# RiskChemi_Monitor_V1_04M1.net
KiCad netlist of a schematic drawn in Altium Designer
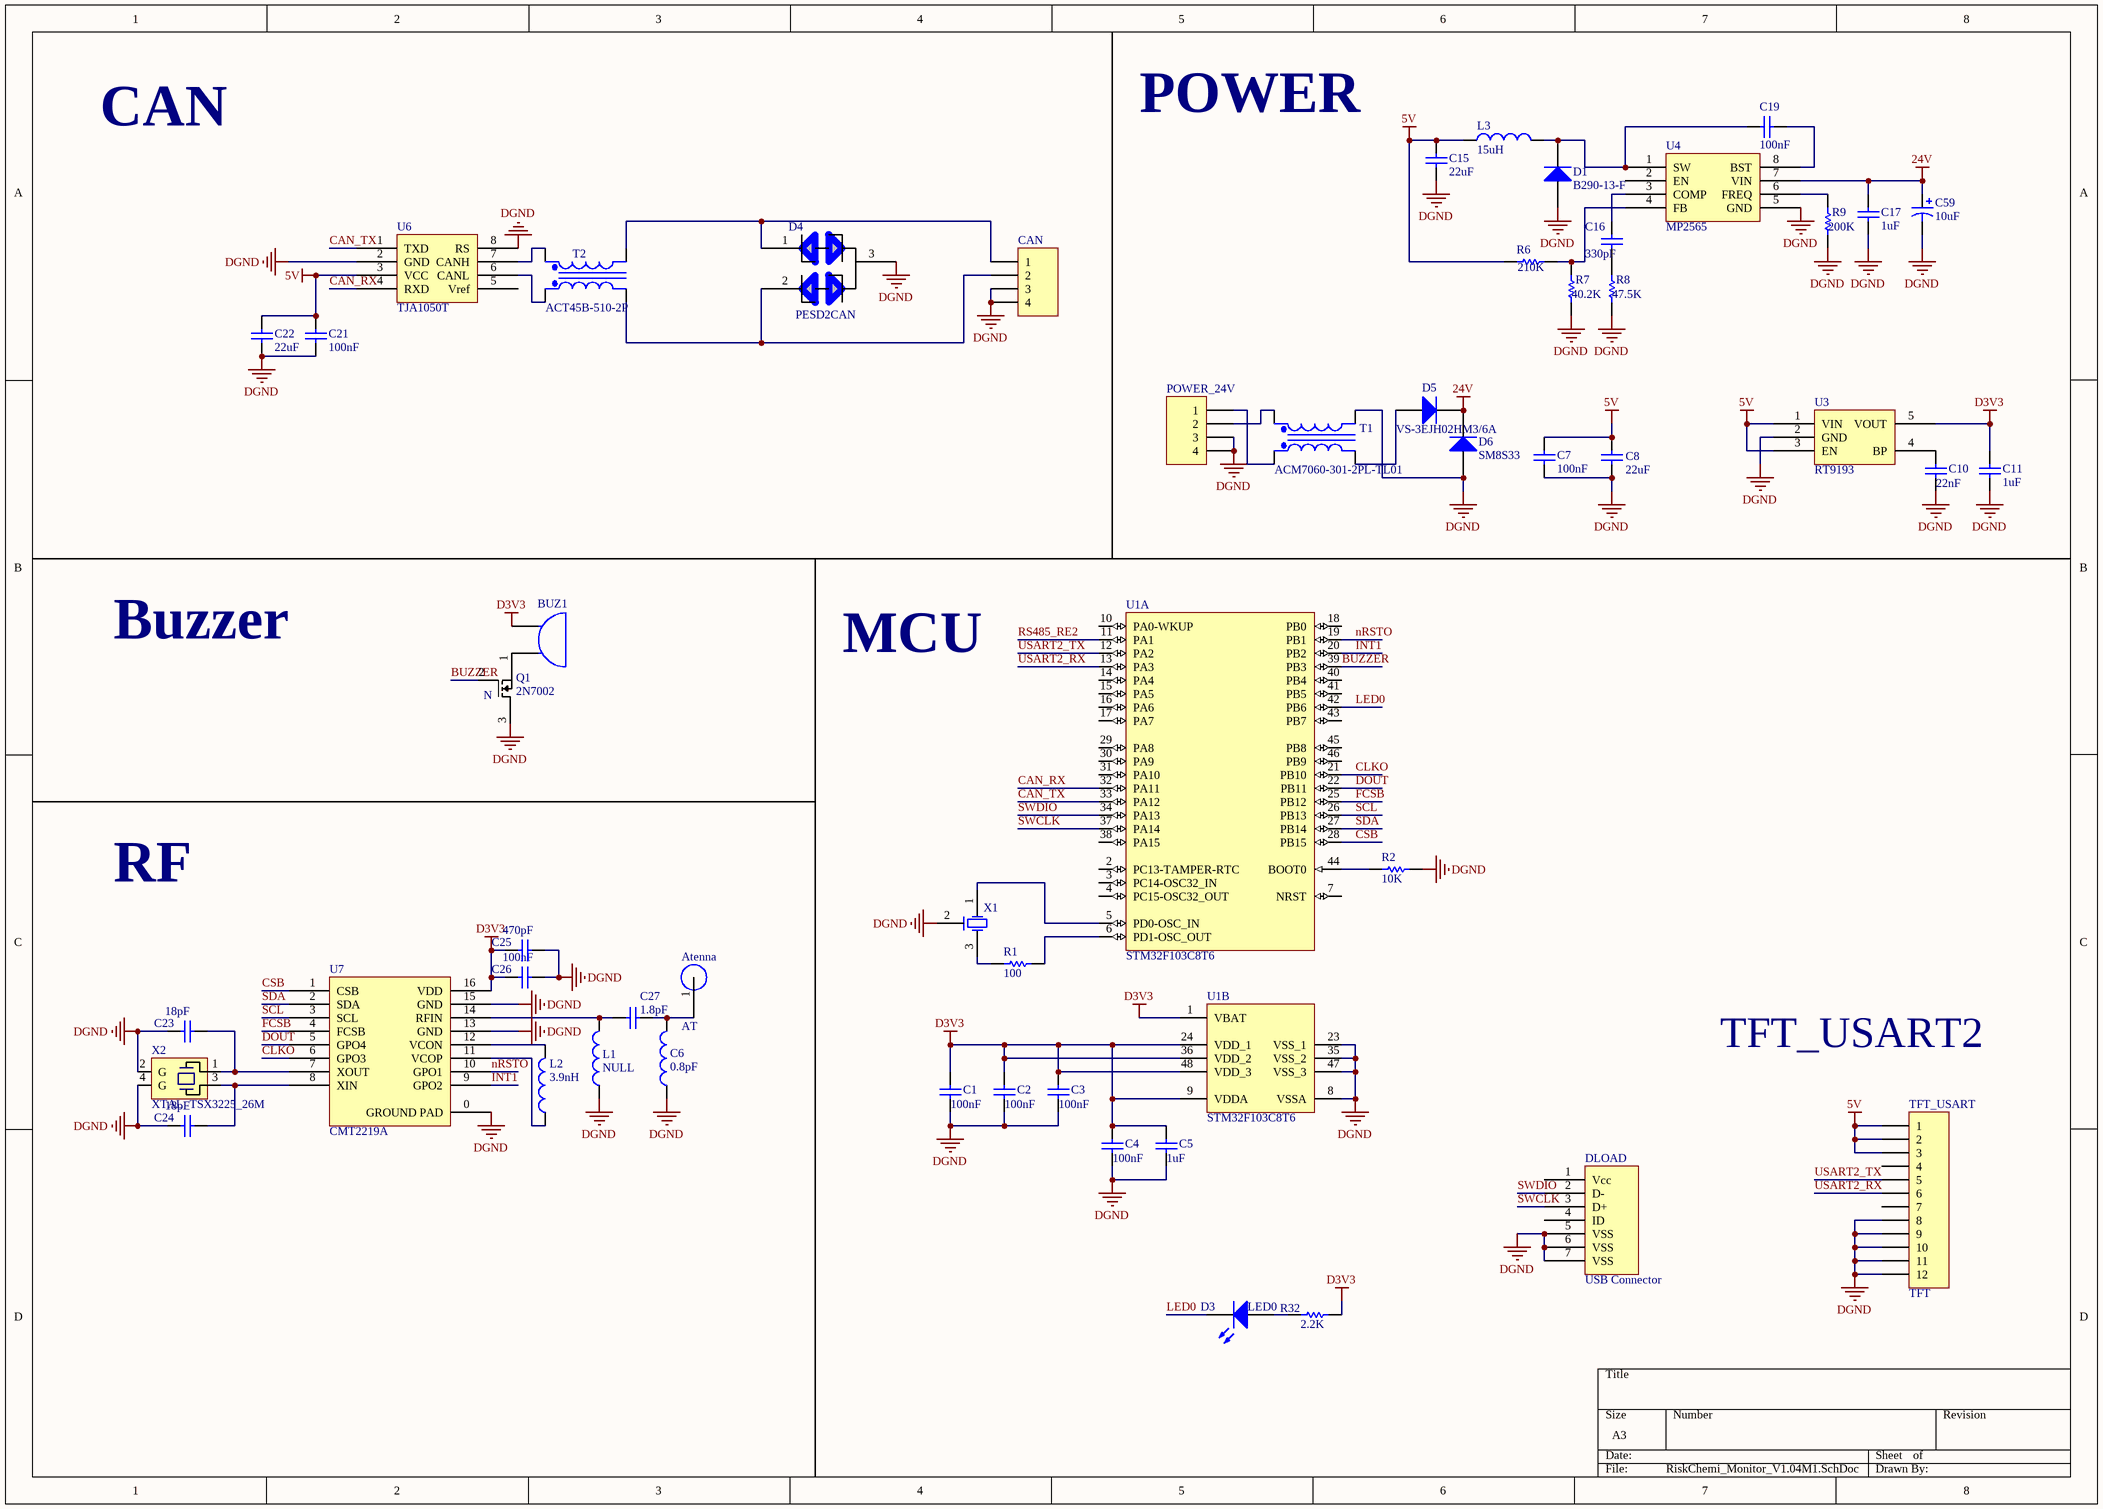
[diagram p0: RiskChemi_Monitor_V1.04M1.SchDoc]

(export (version "E")
  (design (tool "Eeschema 10.0.6"))
  (components
    (comp (ref "Atenna") (value "AT") (footprint "433MHz Atenna") (libsource (lib "MySchlib1") (part "AT")))
    (comp (ref "BUZ1")
      (value "BUZZER")
      (footprint "BUZ0905")
      (description "Buzzer")
      (libsource (lib "杂元件库") (part "BUZZER"))
    )
    (comp (ref "C1")
      (value "100nF")
      (footprint "0603")
      (description "Capacitor")
      (fields (field (name "PUBLISHER") "Altium Limited"))
      (libsource (lib "Miscellaneous Devices") (part "Cap"))
    )
    (comp (ref "C2")
      (value "100nF")
      (footprint "0603")
      (description "Capacitor")
      (fields (field (name "PUBLISHER") "Altium Limited"))
      (libsource (lib "Miscellaneous Devices") (part "Cap"))
    )
    (comp (ref "C3")
      (value "100nF")
      (footprint "0603")
      (description "Capacitor")
      (fields (field (name "PUBLISHER") "Altium Limited"))
      (libsource (lib "Miscellaneous Devices") (part "Cap"))
    )
    (comp (ref "C4")
      (value "100nF")
      (footprint "0603")
      (description "Capacitor")
      (fields (field (name "PUBLISHER") "Altium Limited"))
      (libsource (lib "Miscellaneous Devices") (part "Cap"))
    )
    (comp (ref "C5")
      (value "1uF")
      (footprint "0603")
      (description "Capacitor")
      (fields (field (name "PUBLISHER") "Altium Limited"))
      (libsource (lib "Miscellaneous Devices") (part "Cap"))
    )
    (comp (ref "C6")
      (value "0.8pF")
      (footprint "Miscellaneous Devices:0402")
      (description "Inductor")
      (fields (field (name "PUBLISHER") "Altium Limited"))
      (libsource (lib "Miscellaneous Devices") (part "Inductor"))
    )
    (comp (ref "C7")
      (value "100nF")
      (footprint "0805")
      (description "Capacitor,100V")
      (fields (field (name "PUBLISHER") "Altium Limited"))
      (libsource (lib "Miscellaneous Devices") (part "Cap"))
    )
    (comp (ref "C8")
      (value "22uF")
      (footprint "0805")
      (description "Capacitor")
      (fields (field (name "PUBLISHER") "Altium Limited"))
      (libsource (lib "Miscellaneous Devices") (part "Cap"))
    )
    (comp (ref "C10")
      (value "22nF")
      (footprint "BinFeng:0603")
      (description "Capacitor")
      (fields (field (name "PUBLISHER") "Altium Limited"))
      (libsource (lib "Miscellaneous Devices") (part "Cap"))
    )
    (comp (ref "C11")
      (value "1uF")
      (footprint "BinFeng:0603")
      (description "Capacitor")
      (fields (field (name "PUBLISHER") "Altium Limited"))
      (libsource (lib "Miscellaneous Devices") (part "Cap"))
    )
    (comp (ref "C15")
      (value "22uF")
      (footprint "0805")
      (description "Capacitor,50V")
      (fields (field (name "PUBLISHER") "Altium Limited"))
      (libsource (lib "Miscellaneous Devices") (part "Cap"))
    )
    (comp (ref "C16")
      (value "330pF")
      (footprint "BinFeng:0402")
      (description "Capacitor")
      (fields (field (name "PUBLISHER") "Altium Limited"))
      (libsource (lib "Miscellaneous Devices") (part "Cap"))
    )
    (comp (ref "C17")
      (value "1uF")
      (footprint "0805")
      (description "Capacitor,100V")
      (fields (field (name "PUBLISHER") "Altium Limited"))
      (libsource (lib "Miscellaneous Devices") (part "Cap"))
    )
    (comp (ref "C19")
      (value "100nF")
      (footprint "BinFeng:0402")
      (description "Capacitor")
      (fields (field (name "PUBLISHER") "Altium Limited"))
      (libsource (lib "Miscellaneous Devices") (part "Cap"))
    )
    (comp (ref "C21")
      (value "100nF")
      (footprint "0603")
      (description "Capacitor")
      (fields (field (name "PUBLISHER") "Altium Limited"))
      (libsource (lib "Miscellaneous Devices") (part "Cap"))
    )
    (comp (ref "C22")
      (value "22uF")
      (footprint "0805")
      (description "Capacitor")
      (fields (field (name "PUBLISHER") "Altium Limited"))
      (libsource (lib "Miscellaneous Devices") (part "Cap"))
    )
    (comp (ref "C23")
      (value "18pF")
      (footprint "BinFeng:0402")
      (description "Capacitor")
      (fields (field (name "PUBLISHER") "Altium Limited"))
      (libsource (lib "Miscellaneous Devices") (part "Cap"))
    )
    (comp (ref "C24")
      (value "18pF")
      (footprint "BinFeng:0402")
      (description "Capacitor")
      (fields (field (name "PUBLISHER") "Altium Limited"))
      (libsource (lib "Miscellaneous Devices") (part "Cap"))
    )
    (comp (ref "C25")
      (value "470pF")
      (footprint "BinFeng:0402")
      (description "Capacitor")
      (fields (field (name "PUBLISHER") "Altium Limited"))
      (libsource (lib "Miscellaneous Devices") (part "Cap"))
    )
    (comp (ref "C26")
      (value "100nF")
      (footprint "BinFeng:0603")
      (description "Capacitor")
      (fields (field (name "PUBLISHER") "Altium Limited"))
      (libsource (lib "Miscellaneous Devices") (part "Cap"))
    )
    (comp (ref "C27")
      (value "1.8pF")
      (footprint "BinFeng:nosilk_0402")
      (description "Capacitor")
      (fields (field (name "PUBLISHER") "Altium Limited"))
      (libsource (lib "Miscellaneous Devices") (part "Cap"))
    )
    (comp (ref "C59")
      (value "10uF")
      (footprint "6032_pol")
      (description "Polarized Capacitor (Radial)")
      (fields (field (name "PUBLISHER") "Altium Limited"))
      (libsource (lib "Miscellaneous Devices") (part "Cap Pol1"))
    )
    (comp (ref "CAN")
      (value "Header 4")
      (footprint "C3000VS")
      (description "Header, 4-Pin")
      (fields (field (name "PUBLISHER") "Altium Limited"))
      (libsource (lib "Miscellaneous Connectors") (part "Header 4"))
    )
    (comp (ref "D1")
      (value "B290-13-F")
      (footprint "back:B290")
      (description "Default Diode")
      (fields (field (name "PUBLISHER") "Altium Limited"))
      (libsource (lib "Miscellaneous Devices") (part "Diode"))
    )
    (comp (ref "D3")
      (value "LED0")
      (footprint "LED")
      (description "green LED")
      (fields (field (name "PUBLISHER") "Altium Limited"))
      (libsource (lib "Miscellaneous Devices") (part "LED0"))
    )
    (comp (ref "D4")
      (value "PESD2CAN")
      (footprint "SOT23")
      (libsource (lib "BinFeng_Connectors") (part "PESD1CAN"))
    )
    (comp (ref "D5")
      (value "VS-3EJH02HM3/6A")
      (footprint "back:B290")
      (description "1 Amp General Purpose Rectifier")
      (fields (field (name "PUBLISHER") "Altium Limited"))
      (libsource (lib "Miscellaneous Devices") (part "Diode 1N4007"))
    )
    (comp (ref "D6")
      (value "SM8S33")
      (footprint "SM8S")
      (description "1 Amp General Purpose Rectifier")
      (fields (field (name "PUBLISHER") "Altium Limited"))
      (libsource (lib "Miscellaneous Devices") (part "Diode 1N4007"))
    )
    (comp (ref "DLOAD")
      (value "USB Connector")
      (footprint "Mini_USB")
      (libsource (lib "BinFeng_Connectors") (part "Component_1"))
    )
    (comp (ref "L1")
      (value "NULL")
      (footprint "Miscellaneous Devices:0402")
      (description "Inductor")
      (fields (field (name "PUBLISHER") "Altium Limited"))
      (libsource (lib "Miscellaneous Devices") (part "Inductor"))
    )
    (comp (ref "L2")
      (value "3.9nH")
      (footprint "BinFeng:0603")
      (description "Inductor")
      (fields (field (name "PUBLISHER") "Altium Limited"))
      (libsource (lib "Miscellaneous Devices") (part "Inductor"))
    )
    (comp (ref "L3")
      (value "15uH")
      (footprint "4*4 Inductor")
      (description "Inductor, 1A")
      (fields (field (name "PUBLISHER") "Altium Limited"))
      (libsource (lib "Miscellaneous Devices") (part "Inductor"))
    )
    (comp (ref "POWER_24V")
      (value "Header 4")
      (footprint "C3000VS")
      (description "Header, 4-Pin")
      (fields (field (name "PUBLISHER") "Altium Limited"))
      (libsource (lib "") (part "Header 4_1"))
    )
    (comp (ref "Q1") (value "2N7002") (footprint "2N7002") (libsource (lib "seeder") (part "N-MOSFET")))
    (comp (ref "R1")
      (value "100")
      (footprint "back:0603")
      (description "Resistor")
      (fields (field (name "PUBLISHER") "Altium Limited"))
      (libsource (lib "Miscellaneous Devices") (part "Res1"))
    )
    (comp (ref "R2")
      (value "10K")
      (footprint "back:0603")
      (description "Resistor")
      (fields (field (name "PUBLISHER") "Altium Limited"))
      (libsource (lib "Miscellaneous Devices") (part "Res1"))
    )
    (comp (ref "R6")
      (value "210K")
      (footprint "BinFeng:0402")
      (description "Resistor")
      (fields (field (name "PUBLISHER") "Altium Limited"))
      (libsource (lib "Miscellaneous Devices") (part "Res1"))
    )
    (comp (ref "R7")
      (value "40.2K")
      (footprint "BinFeng:0402")
      (description "Resistor")
      (fields (field (name "PUBLISHER") "Altium Limited"))
      (libsource (lib "Miscellaneous Devices") (part "Res1"))
    )
    (comp (ref "R8")
      (value "47.5K")
      (footprint "BinFeng:0402")
      (description "Resistor")
      (fields (field (name "PUBLISHER") "Altium Limited"))
      (libsource (lib "Miscellaneous Devices") (part "Res1"))
    )
    (comp (ref "R9")
      (value "200K")
      (footprint "BinFeng:0402")
      (description "Resistor")
      (fields (field (name "PUBLISHER") "Altium Limited"))
      (libsource (lib "Miscellaneous Devices") (part "Res1"))
    )
    (comp (ref "R32")
      (value "2.2K")
      (footprint "BinFeng:0603")
      (description "Resistor")
      (fields (field (name "PUBLISHER") "Altium Limited"))
      (libsource (lib "Miscellaneous Devices") (part "Res1"))
    )
    (comp (ref "T1")
      (value "ACM7060-301-2PL-TL01")
      (footprint "ACM7060-301-2P-TL01")
      (description "Transformer (Equivalent Circuit Model)")
      (fields (field (name "PUBLISHER") "Altium Limited"))
      (libsource (lib "Miscellaneous Devices") (part "Trans Eq"))
    )
    (comp (ref "T2")
      (value "ACT45B-510-2P")
      (footprint "ACT45B-510-2P")
      (description "Transformer (Equivalent Circuit Model)")
      (fields (field (name "PUBLISHER") "Altium Limited"))
      (libsource (lib "Miscellaneous Devices") (part "Trans Eq"))
    )
    (comp (ref "TFT_USART")
      (value "TFT")
      (footprint "FCC_10pin_1mm")
      (description "Header, 12-Pin")
      (fields (field (name "PUBLISHER") "Altium Limited"))
      (libsource (lib "Miscellaneous Connectors") (part "Header 12"))
    )
    (comp (ref "U1")
      (value "STM32F103C8T6")
      (footprint "STM-LQFP48_N")
      (libsource (lib "STMicroelectronics STM32 F1") (part "STM32F103C8T6"))
    )
    (comp (ref "U3") (value "RT9193") (footprint "SOT-23-5") (libsource (lib "BinFeng_IC") (part "RT9193")))
    (comp (ref "U4")
      (value "MP2565")
      (footprint "SO8")
      (description "DCDC 4.5V~28V input 1.8V ~5V output low power")
      (libsource (lib "BinFeng_IC") (part "MP1584"))
    )
    (comp (ref "U6")
      (value "TJA1050T")
      (footprint "SO8")
      (description "CAN Tranceiver")
      (libsource (lib "BinFeng_IC") (part "TJA1050T"))
    )
    (comp (ref "U7")
      (value "CMT2219A")
      (footprint "back:QFN16")
      (libsource (lib "BinFeng_IC") (part "CMT2219A"))
    )
    (comp (ref "X1") (value "8M smd") (footprint "8Mhz_XTAL") (libsource (lib "Schlib1") (part "8M smd")))
    (comp (ref "X2")
      (value "XTAL_TSX3225_26M")
      (footprint "XTAL3225")
      (libsource (lib "BinFeng_IC") (part "XTAL_Negative"))
    )
  )
  (nets
    (net (code "1") (name "/BUZZER") (class "Default")
      (node (ref "Q1") (pin "2") (pinfunction "G_2") (pintype "passive"))
      (node (ref "U1") (pin "39") (pinfunction "PB3_39") (pintype "bidirectional"))
    )
    (net (code "2") (name "/CAN_RX") (class "Default")
      (node (ref "U1") (pin "32") (pinfunction "PA11_32") (pintype "bidirectional"))
      (node (ref "U6") (pin "4") (pinfunction "RXD_4") (pintype "passive"))
    )
    (net (code "3") (name "/CAN_TX") (class "Default")
      (node (ref "U1") (pin "33") (pinfunction "PA12_33") (pintype "bidirectional"))
      (node (ref "U6") (pin "1") (pinfunction "TXD_1") (pintype "passive"))
    )
    (net (code "4") (name "/CLKO") (class "Default")
      (node (ref "U1") (pin "21") (pinfunction "PB10_21") (pintype "bidirectional"))
      (node (ref "U7") (pin "6") (pinfunction "GPO3_6") (pintype "passive"))
    )
    (net (code "5") (name "/CSB") (class "Default")
      (node (ref "U1") (pin "28") (pinfunction "PB15_28") (pintype "bidirectional"))
      (node (ref "U7") (pin "1") (pinfunction "CSB_1") (pintype "passive"))
    )
    (net (code "6") (name "/DOUT") (class "Default")
      (node (ref "U1") (pin "22") (pinfunction "PB11_22") (pintype "bidirectional"))
      (node (ref "U7") (pin "5") (pinfunction "GPO4_5") (pintype "passive"))
    )
    (net (code "7") (name "/FCSB") (class "Default")
      (node (ref "U1") (pin "25") (pinfunction "PB12_25") (pintype "bidirectional"))
      (node (ref "U7") (pin "4") (pinfunction "FCSB_4") (pintype "passive"))
    )
    (net (code "8") (name "/INT1") (class "Default")
      (node (ref "U1") (pin "20") (pinfunction "PB2_20") (pintype "bidirectional"))
      (node (ref "U7") (pin "9") (pinfunction "GPO2_9") (pintype "passive"))
    )
    (net (code "9") (name "/LED0") (class "Default")
      (node (ref "D3") (pin "2") (pinfunction "K_2") (pintype "passive"))
      (node (ref "U1") (pin "42") (pinfunction "PB6_42") (pintype "bidirectional"))
    )
    (net (code "10") (name "/RS485_RE2") (class "Default")
      (node (ref "U1") (pin "11") (pinfunction "PA1_11") (pintype "bidirectional"))
    )
    (net (code "11") (name "/SCL") (class "Default")
      (node (ref "U1") (pin "26") (pinfunction "PB13_26") (pintype "bidirectional"))
      (node (ref "U7") (pin "3") (pinfunction "SCL_3") (pintype "passive"))
    )
    (net (code "12") (name "/SDA") (class "Default")
      (node (ref "U1") (pin "27") (pinfunction "PB14_27") (pintype "bidirectional"))
      (node (ref "U7") (pin "2") (pinfunction "SDA_2") (pintype "passive"))
    )
    (net (code "13") (name "/SWCLK") (class "Default")
      (node (ref "DLOAD") (pin "3") (pinfunction "D+_3") (pintype "passive"))
      (node (ref "U1") (pin "37") (pinfunction "PA14_37") (pintype "bidirectional"))
    )
    (net (code "14") (name "/SWDIO") (class "Default")
      (node (ref "DLOAD") (pin "2") (pinfunction "D-_2") (pintype "passive"))
      (node (ref "U1") (pin "34") (pinfunction "PA13_34") (pintype "bidirectional"))
    )
    (net (code "15") (name "/USART2_RX") (class "Default")
      (node (ref "TFT_USART") (pin "6") (pinfunction "6_6") (pintype "passive"))
      (node (ref "U1") (pin "13") (pinfunction "PA3_13") (pintype "bidirectional"))
    )
    (net (code "16") (name "/USART2_TX") (class "Default")
      (node (ref "TFT_USART") (pin "5") (pinfunction "5_5") (pintype "passive"))
      (node (ref "U1") (pin "12") (pinfunction "PA2_12") (pintype "bidirectional"))
    )
    (net (code "17") (name "/nRSTO") (class "Default")
      (node (ref "U1") (pin "19") (pinfunction "PB1_19") (pintype "bidirectional"))
      (node (ref "U7") (pin "10") (pinfunction "GPO1_10") (pintype "passive"))
    )
    (net (code "18") (name "5V") (class "Default")
      (node (ref "C15") (pin "2") (pinfunction "2_2") (pintype "passive"))
      (node (ref "C21") (pin "1") (pinfunction "1_1") (pintype "passive"))
      (node (ref "C22") (pin "2") (pinfunction "2_2") (pintype "passive"))
      (node (ref "C7") (pin "2") (pinfunction "2_2") (pintype "passive"))
      (node (ref "C8") (pin "2") (pinfunction "2_2") (pintype "passive"))
      (node (ref "L3") (pin "1") (pinfunction "1_1") (pintype "passive"))
      (node (ref "R6") (pin "2") (pinfunction "2_2") (pintype "passive"))
      (node (ref "TFT_USART") (pin "1") (pinfunction "1_1") (pintype "passive"))
      (node (ref "TFT_USART") (pin "2") (pinfunction "2_2") (pintype "passive"))
      (node (ref "TFT_USART") (pin "3") (pinfunction "3_3") (pintype "passive"))
      (node (ref "U3") (pin "1") (pinfunction "VIN_1") (pintype "passive"))
      (node (ref "U3") (pin "3") (pinfunction "EN_3") (pintype "passive"))
      (node (ref "U6") (pin "3") (pinfunction "VCC_3") (pintype "passive"))
    )
    (net (code "19") (name "24V") (class "Default")
      (node (ref "C17") (pin "2") (pinfunction "2_2") (pintype "passive"))
      (node (ref "C59") (pin "1") (pinfunction "1_1") (pintype "passive"))
      (node (ref "D5") (pin "2") (pinfunction "K_2") (pintype "passive"))
      (node (ref "D6") (pin "2") (pinfunction "K_2") (pintype "passive"))
      (node (ref "U4") (pin "7") (pinfunction "VIN_7") (pintype "passive"))
    )
    (net (code "20") (name "D3V3") (class "Default")
      (node (ref "BUZ1") (pin "1") (pinfunction "A_1") (pintype "passive"))
      (node (ref "C1") (pin "2") (pinfunction "2_2") (pintype "passive"))
      (node (ref "C11") (pin "2") (pinfunction "2_2") (pintype "passive"))
      (node (ref "C2") (pin "2") (pinfunction "2_2") (pintype "passive"))
      (node (ref "C25") (pin "2") (pinfunction "2_2") (pintype "passive"))
      (node (ref "C26") (pin "2") (pinfunction "2_2") (pintype "passive"))
      (node (ref "C3") (pin "2") (pinfunction "2_2") (pintype "passive"))
      (node (ref "C4") (pin "2") (pinfunction "2_2") (pintype "passive"))
      (node (ref "C5") (pin "2") (pinfunction "2_2") (pintype "passive"))
      (node (ref "R32") (pin "1") (pinfunction "1_1") (pintype "passive"))
      (node (ref "U1") (pin "1") (pinfunction "VBAT_1") (pintype "power_in"))
      (node (ref "U1") (pin "24") (pinfunction "VDD_1_24") (pintype "power_in"))
      (node (ref "U1") (pin "36") (pinfunction "VDD_2_36") (pintype "power_in"))
      (node (ref "U1") (pin "48") (pinfunction "VDD_3_48") (pintype "power_in"))
      (node (ref "U1") (pin "9") (pinfunction "VDDA_9") (pintype "power_in"))
      (node (ref "U3") (pin "5") (pinfunction "VOUT_5") (pintype "passive"))
      (node (ref "U7") (pin "16") (pinfunction "VDD_16") (pintype "passive"))
    )
    (net (code "21") (name "DGND") (class "Default")
      (node (ref "C1") (pin "1") (pinfunction "1_1") (pintype "passive"))
      (node (ref "C10") (pin "1") (pinfunction "1_1") (pintype "passive"))
      (node (ref "C11") (pin "1") (pinfunction "1_1") (pintype "passive"))
      (node (ref "C15") (pin "1") (pinfunction "1_1") (pintype "passive"))
      (node (ref "C17") (pin "1") (pinfunction "1_1") (pintype "passive"))
      (node (ref "C2") (pin "1") (pinfunction "1_1") (pintype "passive"))
      (node (ref "C21") (pin "2") (pinfunction "2_2") (pintype "passive"))
      (node (ref "C22") (pin "1") (pinfunction "1_1") (pintype "passive"))
      (node (ref "C23") (pin "2") (pinfunction "2_2") (pintype "passive"))
      (node (ref "C24") (pin "2") (pinfunction "2_2") (pintype "passive"))
      (node (ref "C25") (pin "1") (pinfunction "1_1") (pintype "passive"))
      (node (ref "C26") (pin "1") (pinfunction "1_1") (pintype "passive"))
      (node (ref "C3") (pin "1") (pinfunction "1_1") (pintype "passive"))
      (node (ref "C4") (pin "1") (pinfunction "1_1") (pintype "passive"))
      (node (ref "C5") (pin "1") (pinfunction "1_1") (pintype "passive"))
      (node (ref "C59") (pin "2") (pinfunction "2_2") (pintype "passive"))
      (node (ref "C6") (pin "1") (pinfunction "1_1") (pintype "passive"))
      (node (ref "C7") (pin "1") (pinfunction "1_1") (pintype "passive"))
      (node (ref "C8") (pin "1") (pinfunction "1_1") (pintype "passive"))
      (node (ref "CAN") (pin "3") (pinfunction "3_3") (pintype "passive"))
      (node (ref "CAN") (pin "4") (pinfunction "4_4") (pintype "passive"))
      (node (ref "D1") (pin "1") (pinfunction "A_1") (pintype "passive"))
      (node (ref "D4") (pin "3") (pinfunction "13_3") (pintype "passive"))
      (node (ref "D6") (pin "1") (pinfunction "A_1") (pintype "passive"))
      (node (ref "DLOAD") (pin "5") (pinfunction "VSS_5") (pintype "passive"))
      (node (ref "DLOAD") (pin "6") (pinfunction "VSS_6") (pintype "passive"))
      (node (ref "DLOAD") (pin "7") (pinfunction "VSS_7") (pintype "passive"))
      (node (ref "L1") (pin "1") (pinfunction "1_1") (pintype "passive"))
      (node (ref "POWER_24V") (pin "3") (pinfunction "3_3") (pintype "passive"))
      (node (ref "POWER_24V") (pin "4") (pinfunction "4_4") (pintype "passive"))
      (node (ref "Q1") (pin "3") (pinfunction "S_3") (pintype "passive"))
      (node (ref "R2") (pin "2") (pinfunction "2_2") (pintype "passive"))
      (node (ref "R7") (pin "1") (pinfunction "1_1") (pintype "passive"))
      (node (ref "R8") (pin "1") (pinfunction "1_1") (pintype "passive"))
      (node (ref "R9") (pin "1") (pinfunction "1_1") (pintype "passive"))
      (node (ref "T1") (pin "4") (pinfunction "Sec-_4") (pintype "passive"))
      (node (ref "TFT_USART") (pin "10") (pinfunction "10_10") (pintype "passive"))
      (node (ref "TFT_USART") (pin "11") (pinfunction "11_11") (pintype "passive"))
      (node (ref "TFT_USART") (pin "12") (pinfunction "12_12") (pintype "passive"))
      (node (ref "TFT_USART") (pin "8") (pinfunction "8_8") (pintype "passive"))
      (node (ref "TFT_USART") (pin "9") (pinfunction "9_9") (pintype "passive"))
      (node (ref "U1") (pin "23") (pinfunction "VSS_1_23") (pintype "power_in"))
      (node (ref "U1") (pin "35") (pinfunction "VSS_2_35") (pintype "power_in"))
      (node (ref "U1") (pin "47") (pinfunction "VSS_3_47") (pintype "power_in"))
      (node (ref "U1") (pin "8") (pinfunction "VSSA_8") (pintype "power_in"))
      (node (ref "U3") (pin "2") (pinfunction "GND_2") (pintype "passive"))
      (node (ref "U4") (pin "5") (pinfunction "GND_5") (pintype "passive"))
      (node (ref "U6") (pin "2") (pinfunction "GND_2") (pintype "passive"))
      (node (ref "U6") (pin "8") (pinfunction "RS_8") (pintype "passive"))
      (node (ref "U7") (pin "0") (pinfunction "GROUND_PAD_0") (pintype "passive"))
      (node (ref "U7") (pin "13") (pinfunction "GND_13") (pintype "passive"))
      (node (ref "U7") (pin "15") (pinfunction "GND_15") (pintype "passive"))
      (node (ref "X1") (pin "2") (pinfunction "GND_2") (pintype "passive"))
      (node (ref "X2") (pin "2") (pinfunction "G_2") (pintype "passive"))
      (node (ref "X2") (pin "4") (pinfunction "G_4") (pintype "passive"))
    )
    (net (code "22") (name "Net-(Atenna-Pad1)") (class "Default")
      (node (ref "Atenna") (pin "1") (pinfunction "1_1") (pintype "passive"))
      (node (ref "C27") (pin "1") (pinfunction "1_1") (pintype "passive"))
      (node (ref "C6") (pin "2") (pinfunction "2_2") (pintype "passive"))
    )
    (net (code "23") (name "Net-(BUZ1-B)") (class "Default")
      (node (ref "BUZ1") (pin "2") (pinfunction "B_2") (pintype "passive"))
      (node (ref "Q1") (pin "1") (pinfunction "D_1") (pintype "passive"))
    )
    (net (code "24") (name "Net-(C16-Pad2)") (class "Default")
      (node (ref "C16") (pin "2") (pinfunction "2_2") (pintype "passive"))
      (node (ref "R8") (pin "2") (pinfunction "2_2") (pintype "passive"))
    )
    (net (code "25") (name "Net-(D1-K)") (class "Default")
      (node (ref "C19") (pin "2") (pinfunction "2_2") (pintype "passive"))
      (node (ref "D1") (pin "2") (pinfunction "K_2") (pintype "passive"))
      (node (ref "L3") (pin "2") (pinfunction "2_2") (pintype "passive"))
      (node (ref "U4") (pin "1") (pinfunction "SW_1") (pintype "passive"))
    )
    (net (code "26") (name "Net-(D3-A)") (class "Default")
      (node (ref "D3") (pin "1") (pinfunction "A_1") (pintype "passive"))
      (node (ref "R32") (pin "2") (pinfunction "2_2") (pintype "passive"))
    )
    (net (code "27") (name "Net-(D4-11)") (class "Default")
      (node (ref "CAN") (pin "1") (pinfunction "1_1") (pintype "passive"))
      (node (ref "D4") (pin "1") (pinfunction "11_1") (pintype "passive"))
      (node (ref "T2") (pin "4") (pinfunction "Sec-_4") (pintype "passive"))
    )
    (net (code "28") (name "Net-(D4-12)") (class "Default")
      (node (ref "CAN") (pin "2") (pinfunction "2_2") (pintype "passive"))
      (node (ref "D4") (pin "2") (pinfunction "12_2") (pintype "passive"))
      (node (ref "T2") (pin "2") (pinfunction "Pri-_2") (pintype "passive"))
    )
    (net (code "29") (name "Net-(D5-A)") (class "Default")
      (node (ref "D5") (pin "1") (pinfunction "A_1") (pintype "passive"))
      (node (ref "T1") (pin "2") (pinfunction "Pri-_2") (pintype "passive"))
    )
    (net (code "30") (name "Net-(T1-Pri+)") (class "Default")
      (node (ref "POWER_24V") (pin "1") (pinfunction "1_1") (pintype "passive"))
      (node (ref "T1") (pin "1") (pinfunction "Pri+_1") (pintype "passive"))
    )
    (net (code "31") (name "Net-(T1-Sec+)") (class "Default")
      (node (ref "POWER_24V") (pin "2") (pinfunction "2_2") (pintype "passive"))
      (node (ref "T1") (pin "3") (pinfunction "Sec+_3") (pintype "passive"))
    )
    (net (code "32") (name "Net-(T2-Pri+)") (class "Default")
      (node (ref "T2") (pin "1") (pinfunction "Pri+_1") (pintype "passive"))
      (node (ref "U6") (pin "6") (pinfunction "CANL_6") (pintype "passive"))
    )
    (net (code "33") (name "Net-(T2-Sec+)") (class "Default")
      (node (ref "T2") (pin "3") (pinfunction "Sec+_3") (pintype "passive"))
      (node (ref "U6") (pin "7") (pinfunction "CANH_7") (pintype "passive"))
    )
    (net (code "34") (name "Net-(U1A-BOOT0)") (class "Default")
      (node (ref "R2") (pin "1") (pinfunction "1_1") (pintype "passive"))
      (node (ref "U1") (pin "44") (pinfunction "BOOT0_44") (pintype "input"))
    )
    (net (code "35") (name "Net-(U1A-PD0-OSC_IN)") (class "Default")
      (node (ref "U1") (pin "5") (pinfunction "PD0-OSC_IN_5") (pintype "bidirectional"))
      (node (ref "X1") (pin "1") (pinfunction "OSC1_1") (pintype "passive"))
    )
    (net (code "36") (name "Net-(U1A-PD1-OSC_OUT)") (class "Default")
      (node (ref "R1") (pin "2") (pinfunction "2_2") (pintype "passive"))
      (node (ref "U1") (pin "6") (pinfunction "PD1-OSC_OUT_6") (pintype "bidirectional"))
    )
    (net (code "37") (name "Net-(U3-BP)") (class "Default")
      (node (ref "C10") (pin "2") (pinfunction "2_2") (pintype "passive"))
      (node (ref "U3") (pin "4") (pinfunction "BP_4") (pintype "passive"))
    )
    (net (code "38") (name "Net-(U4-BST)") (class "Default")
      (node (ref "C19") (pin "1") (pinfunction "1_1") (pintype "passive"))
      (node (ref "U4") (pin "8") (pinfunction "BST_8") (pintype "passive"))
    )
    (net (code "39") (name "Net-(U4-COMP)") (class "Default")
      (node (ref "C16") (pin "1") (pinfunction "1_1") (pintype "passive"))
      (node (ref "U4") (pin "3") (pinfunction "COMP_3") (pintype "passive"))
    )
    (net (code "40") (name "Net-(U4-FB)") (class "Default")
      (node (ref "R6") (pin "1") (pinfunction "1_1") (pintype "passive"))
      (node (ref "R7") (pin "2") (pinfunction "2_2") (pintype "passive"))
      (node (ref "U4") (pin "4") (pinfunction "FB_4") (pintype "passive"))
    )
    (net (code "41") (name "Net-(U4-FREQ)") (class "Default")
      (node (ref "R9") (pin "2") (pinfunction "2_2") (pintype "passive"))
      (node (ref "U4") (pin "6") (pinfunction "FREQ_6") (pintype "passive"))
    )
    (net (code "42") (name "Net-(U7-RFIN)") (class "Default")
      (node (ref "C27") (pin "2") (pinfunction "2_2") (pintype "passive"))
      (node (ref "L1") (pin "2") (pinfunction "2_2") (pintype "passive"))
      (node (ref "U7") (pin "14") (pinfunction "RFIN_14") (pintype "passive"))
    )
    (net (code "43") (name "Net-(U7-VCON)") (class "Default")
      (node (ref "L2") (pin "2") (pinfunction "2_2") (pintype "passive"))
      (node (ref "U7") (pin "12") (pinfunction "VCON_12") (pintype "passive"))
    )
    (net (code "44") (name "Net-(U7-VCOP)") (class "Default")
      (node (ref "L2") (pin "1") (pinfunction "1_1") (pintype "passive"))
      (node (ref "U7") (pin "11") (pinfunction "VCOP_11") (pintype "passive"))
    )
    (net (code "45") (name "Net-(U7-XIN)") (class "Default")
      (node (ref "C24") (pin "1") (pinfunction "1_1") (pintype "passive"))
      (node (ref "U7") (pin "8") (pinfunction "XIN_8") (pintype "passive"))
      (node (ref "X2") (pin "3") (pintype "passive"))
    )
    (net (code "46") (name "Net-(U7-XOUT)") (class "Default")
      (node (ref "C23") (pin "1") (pinfunction "1_1") (pintype "passive"))
      (node (ref "U7") (pin "7") (pinfunction "XOUT_7") (pintype "passive"))
      (node (ref "X2") (pin "1") (pintype "passive"))
    )
    (net (code "47") (name "Net-(X1-OSC2)") (class "Default")
      (node (ref "R1") (pin "1") (pinfunction "1_1") (pintype "passive"))
      (node (ref "X1") (pin "3") (pinfunction "OSC2_3") (pintype "passive"))
    )
    (net (code "48") (name "unconnected-(DLOAD-ID-Pad4)") (class "Default")
      (node (ref "DLOAD") (pin "4") (pinfunction "ID_4") (pintype "passive"))
    )
    (net (code "49") (name "unconnected-(DLOAD-Vcc-Pad1)") (class "Default")
      (node (ref "DLOAD") (pin "1") (pinfunction "Vcc_1") (pintype "passive"))
    )
    (net (code "50") (name "unconnected-(TFT_USART-Pad4)") (class "Default")
      (node (ref "TFT_USART") (pin "4") (pinfunction "4_4") (pintype "passive"))
    )
    (net (code "51") (name "unconnected-(TFT_USART-Pad7)") (class "Default")
      (node (ref "TFT_USART") (pin "7") (pinfunction "7_7") (pintype "passive"))
    )
    (net (code "52") (name "unconnected-(U1A-NRST-Pad7)") (class "Default")
      (node (ref "U1") (pin "7") (pinfunction "NRST_7") (pintype "bidirectional"))
    )
    (net (code "53") (name "unconnected-(U1A-PA0-WKUP-Pad10)") (class "Default")
      (node (ref "U1") (pin "10") (pinfunction "PA0-WKUP_10") (pintype "bidirectional"))
    )
    (net (code "54") (name "unconnected-(U1A-PA4-Pad14)") (class "Default")
      (node (ref "U1") (pin "14") (pinfunction "PA4_14") (pintype "bidirectional"))
    )
    (net (code "55") (name "unconnected-(U1A-PA5-Pad15)") (class "Default")
      (node (ref "U1") (pin "15") (pinfunction "PA5_15") (pintype "bidirectional"))
    )
    (net (code "56") (name "unconnected-(U1A-PA6-Pad16)") (class "Default")
      (node (ref "U1") (pin "16") (pinfunction "PA6_16") (pintype "bidirectional"))
    )
    (net (code "57") (name "unconnected-(U1A-PA7-Pad17)") (class "Default")
      (node (ref "U1") (pin "17") (pinfunction "PA7_17") (pintype "bidirectional"))
    )
    (net (code "58") (name "unconnected-(U1A-PA8-Pad29)") (class "Default")
      (node (ref "U1") (pin "29") (pinfunction "PA8_29") (pintype "bidirectional"))
    )
    (net (code "59") (name "unconnected-(U1A-PA9-Pad30)") (class "Default")
      (node (ref "U1") (pin "30") (pinfunction "PA9_30") (pintype "bidirectional"))
    )
    (net (code "60") (name "unconnected-(U1A-PA10-Pad31)") (class "Default")
      (node (ref "U1") (pin "31") (pinfunction "PA10_31") (pintype "bidirectional"))
    )
    (net (code "61") (name "unconnected-(U1A-PA15-Pad38)") (class "Default")
      (node (ref "U1") (pin "38") (pinfunction "PA15_38") (pintype "bidirectional"))
    )
    (net (code "62") (name "unconnected-(U1A-PB0-Pad18)") (class "Default")
      (node (ref "U1") (pin "18") (pinfunction "PB0_18") (pintype "bidirectional"))
    )
    (net (code "63") (name "unconnected-(U1A-PB4-Pad40)") (class "Default")
      (node (ref "U1") (pin "40") (pinfunction "PB4_40") (pintype "bidirectional"))
    )
    (net (code "64") (name "unconnected-(U1A-PB5-Pad41)") (class "Default")
      (node (ref "U1") (pin "41") (pinfunction "PB5_41") (pintype "bidirectional"))
    )
    (net (code "65") (name "unconnected-(U1A-PB7-Pad43)") (class "Default")
      (node (ref "U1") (pin "43") (pinfunction "PB7_43") (pintype "bidirectional"))
    )
    (net (code "66") (name "unconnected-(U1A-PB8-Pad45)") (class "Default")
      (node (ref "U1") (pin "45") (pinfunction "PB8_45") (pintype "bidirectional"))
    )
    (net (code "67") (name "unconnected-(U1A-PB9-Pad46)") (class "Default")
      (node (ref "U1") (pin "46") (pinfunction "PB9_46") (pintype "bidirectional"))
    )
    (net (code "68") (name "unconnected-(U1A-PC13-TAMPER-RTC-Pad2)") (class "Default")
      (node (ref "U1") (pin "2") (pinfunction "PC13-TAMPER-RTC_2") (pintype "bidirectional"))
    )
    (net (code "69") (name "unconnected-(U1A-PC14-OSC32_IN-Pad3)") (class "Default")
      (node (ref "U1") (pin "3") (pinfunction "PC14-OSC32_IN_3") (pintype "bidirectional"))
    )
    (net (code "70") (name "unconnected-(U1A-PC15-OSC32_OUT-Pad4)") (class "Default")
      (node (ref "U1") (pin "4") (pinfunction "PC15-OSC32_OUT_4") (pintype "bidirectional"))
    )
    (net (code "71") (name "unconnected-(U4-EN-Pad2)") (class "Default")
      (node (ref "U4") (pin "2") (pinfunction "EN_2") (pintype "passive"))
    )
    (net (code "72") (name "unconnected-(U6-Vref-Pad5)") (class "Default")
      (node (ref "U6") (pin "5") (pinfunction "Vref_5") (pintype "passive"))
    )
  )
)
